# -_V1_3.net
KiCad netlist of a schematic drawn in EasyEDA Pro
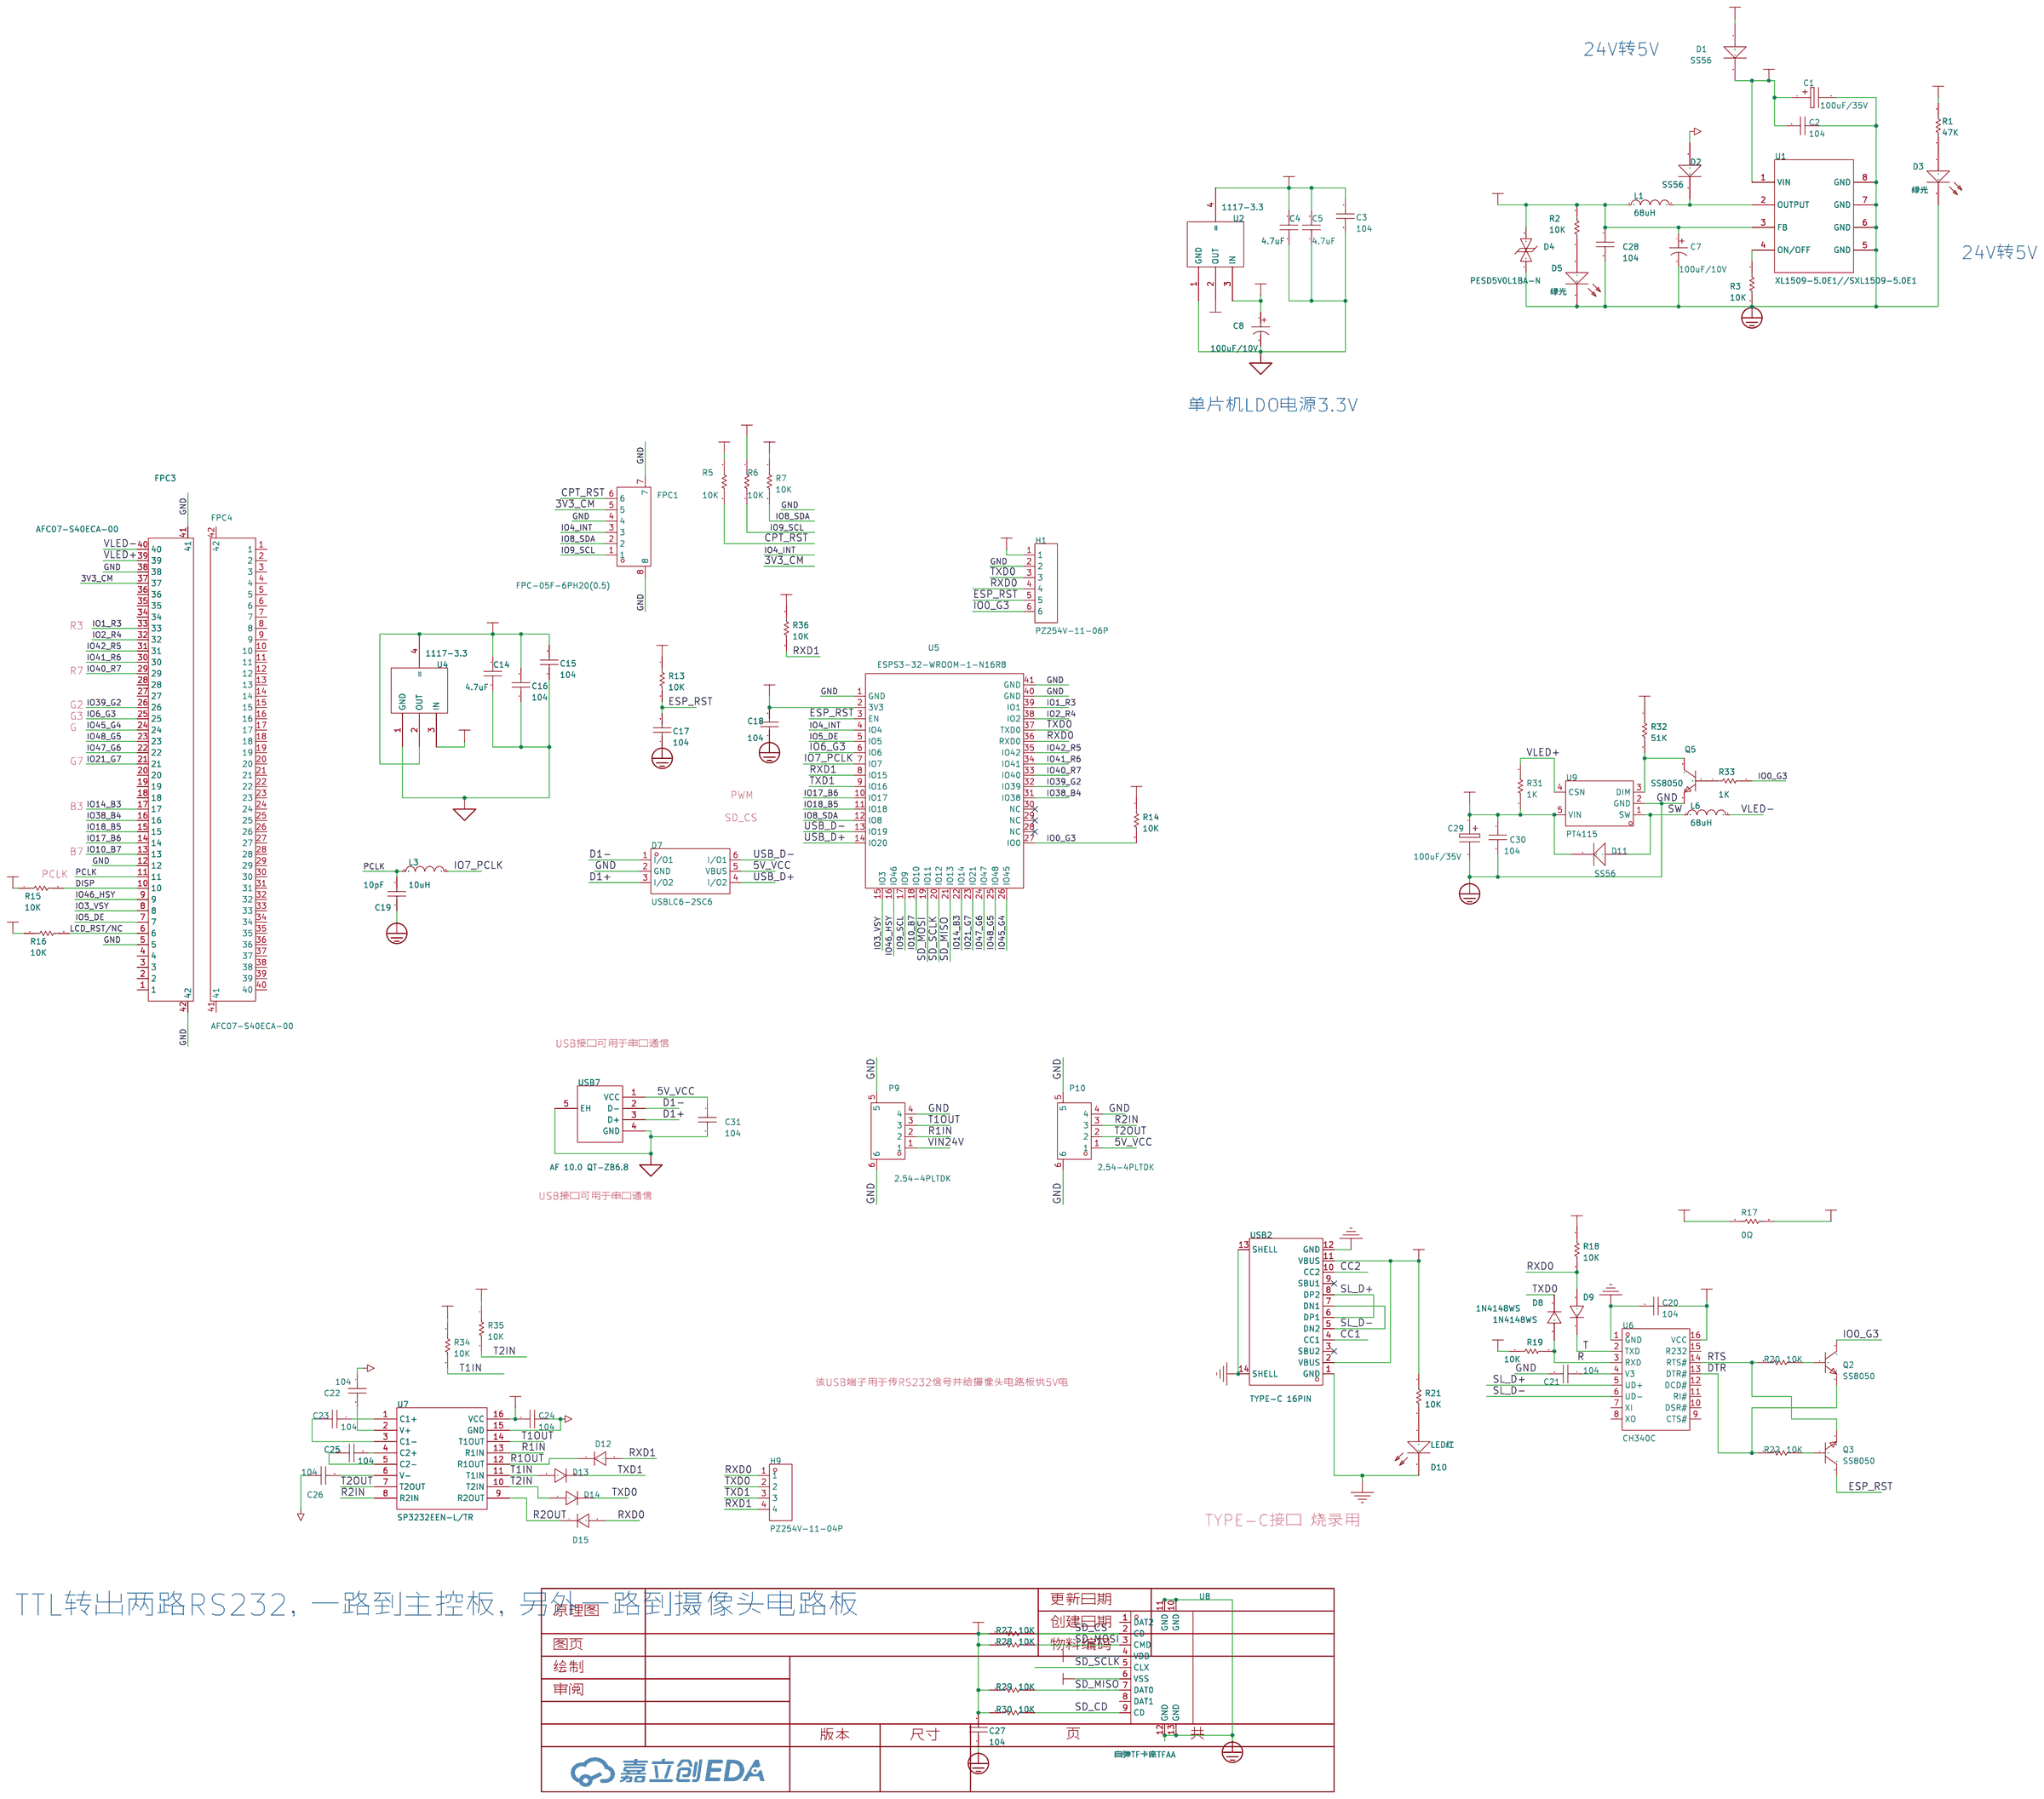
[diagram p0: schematic sheet]

(export (version "E")
  (design (tool "Eeschema 10.0.6"))
  (components
    (comp (ref "C1")
      (value "100uF/35V")
      (footprint "easyedapro:电解电容贴片10x10")
      (libsource (lib "easyedapro") (part "ELECTRO1"))
    )
    (comp (ref "C2")
      (value "104")
      (footprint "easyedapro:0603C")
      (description "Capacitor (Semiconductor SIM Model)")
      (libsource (lib "easyedapro") (part "Cap Semi"))
    )
    (comp (ref "C3")
      (value "104")
      (footprint "easyedapro:0603C")
      (description "Capacitor (Semiconductor SIM Model)")
      (libsource (lib "easyedapro") (part "Cap Semi"))
    )
    (comp (ref "C4") (value "4.7uF") (libsource (lib "easyedapro") (part "CAP")))
    (comp (ref "C5") (value "4.7uF") (libsource (lib "easyedapro") (part "CAP")))
    (comp (ref "C7")
      (value "100uF/10V")
      (footprint "easyedapro:CAP-SMD_BD5.0-L5.3-W5.3-RD")
      (fields (field (name "Manufacturer Part") "CS1A101M-CRD54") (field (name "Manufacturer") "ST(先科)"))
      (libsource (lib "easyedapro") (part "CS1A101M-CRD54"))
    )
    (comp (ref "C8")
      (value "100uF/10V")
      (footprint "easyedapro:CAP-SMD_BD5.0-L5.3-W5.3-RD")
      (fields (field (name "Manufacturer Part") "CS1A101M-CRD54") (field (name "Manufacturer") "ST(先科)"))
      (libsource (lib "easyedapro") (part "CS1A101M-CRD54"))
    )
    (comp (ref "C14") (value "4.7uF") (libsource (lib "easyedapro") (part "CAP")))
    (comp (ref "C15")
      (value "104")
      (footprint "easyedapro:0603C")
      (description "Capacitor (Semiconductor SIM Model)")
      (libsource (lib "easyedapro") (part "Cap Semi"))
    )
    (comp (ref "C16")
      (value "104")
      (footprint "easyedapro:0603C")
      (description "Capacitor (Semiconductor SIM Model)")
      (libsource (lib "easyedapro") (part "Cap Semi"))
    )
    (comp (ref "C17")
      (value "104")
      (footprint "easyedapro:0603C")
      (description "Capacitor (Semiconductor SIM Model)")
      (libsource (lib "easyedapro") (part "Cap Semi"))
    )
    (comp (ref "C18")
      (value "104")
      (footprint "easyedapro:0603C")
      (description "Capacitor (Semiconductor SIM Model)")
      (libsource (lib "easyedapro") (part "Cap Semi"))
    )
    (comp (ref "C19")
      (value "10pF")
      (footprint "easyedapro:0603C")
      (description "Capacitor (Semiconductor SIM Model)")
      (libsource (lib "easyedapro") (part "Cap Semi"))
    )
    (comp (ref "C20")
      (value "104")
      (footprint "easyedapro:0603C")
      (description "Capacitor (Semiconductor SIM Model)")
      (libsource (lib "easyedapro") (part "Cap Semi"))
    )
    (comp (ref "C21")
      (value "104")
      (footprint "easyedapro:0603C")
      (description "Capacitor (Semiconductor SIM Model)")
      (libsource (lib "easyedapro") (part "Cap Semi"))
    )
    (comp (ref "C22")
      (value "104")
      (footprint "easyedapro:0603C")
      (description "Capacitor (Semiconductor SIM Model)")
      (libsource (lib "easyedapro") (part "Cap Semi"))
    )
    (comp (ref "C23")
      (value "104")
      (footprint "easyedapro:0603C")
      (description "Capacitor (Semiconductor SIM Model)")
      (libsource (lib "easyedapro") (part "Cap Semi"))
    )
    (comp (ref "C24")
      (value "104")
      (footprint "easyedapro:0603C")
      (description "Capacitor (Semiconductor SIM Model)")
      (libsource (lib "easyedapro") (part "Cap Semi"))
    )
    (comp (ref "C25")
      (value "104")
      (footprint "easyedapro:0603C")
      (description "Capacitor (Semiconductor SIM Model)")
      (libsource (lib "easyedapro") (part "Cap Semi"))
    )
    (comp (ref "C26")
      (value "104")
      (footprint "easyedapro:0603C")
      (description "Capacitor (Semiconductor SIM Model)")
      (libsource (lib "easyedapro") (part "Cap Semi"))
    )
    (comp (ref "C27")
      (value "104")
      (footprint "easyedapro:11")
      (description "Capacitor (Semiconductor SIM Model)")
      (libsource (lib "easyedapro") (part "Cap Semi"))
    )
    (comp (ref "C28")
      (value "104")
      (footprint "easyedapro:0603C")
      (description "Capacitor (Semiconductor SIM Model)")
      (libsource (lib "easyedapro") (part "Cap Semi"))
    )
    (comp (ref "C29")
      (value "100uF/35V")
      (footprint "easyedapro:电解电容贴片10x10")
      (libsource (lib "easyedapro") (part "ELECTRO1"))
    )
    (comp (ref "C30")
      (value "104")
      (footprint "easyedapro:0603C")
      (description "Capacitor (Semiconductor SIM Model)")
      (libsource (lib "easyedapro") (part "Cap Semi"))
    )
    (comp (ref "C31")
      (value "104")
      (footprint "easyedapro:0603C")
      (description "Capacitor (Semiconductor SIM Model)")
      (libsource (lib "easyedapro") (part "Cap Semi"))
    )
    (comp (ref "D1") (value "SS56") (footprint "easyedapro:SMA") (libsource (lib "") (part "1N4148_1")))
    (comp (ref "D2") (value "SS56") (libsource (lib "easyedapro") (part "1N4148")))
    (comp (ref "D3")
      (value "绿光")
      (footprint "easyedapro:0603LED")
      (libsource (lib "easyedapro") (part "LED"))
    )
    (comp (ref "D4")
      (value "PESD5V0L1BA-N")
      (footprint "easyedapro:SOD-523_L1.2-W0.8-LS1.6-BI")
      (description "极性:Bidirectional;反向关断电压（典型值）:5V (Max);击穿电压（最小值）:6V;箝位电压:15V;峰值脉冲电流（10/1000us）:5A (8/20us);")
      (fields (field (name "Manufacturer") "BORN伯恩半导体"))
      (libsource (lib "easyedapro") (part "PESD5V0S1BBN"))
    )
    (comp (ref "D5")
      (value "绿光")
      (footprint "easyedapro:0603LED")
      (libsource (lib "easyedapro") (part "LED"))
    )
    (comp (ref "D7")
      (value "USBLC6-2SC6")
      (footprint "easyedapro:SOT-23-6_L2.9-W1.6-P0.95-LS2.8-BL")
      (description "最大钳位电压:15V;击穿电压:6V;")
      (fields (field (name "Manufacturer") "UMW(友台半导体)"))
      (libsource (lib "easyedapro") (part "USBLC6-2SC6_C2687116"))
    )
    (comp (ref "D8")
      (value "1N4148WS")
      (footprint "easyedapro:SOD-323_L1.8-W1.3-LS2.5-RD")
      (description "二极管配置:独立式;正向压降(Vf):1.25V@150mA;直流反向耐压(Vr):100V;整流电流:150mA;反向恢复时间(Trr):4ns;")
      (fields (field (name "Manufacturer") "CJ(江苏长电/长晶)"))
      (libsource (lib "easyedapro") (part "1N4148WS T4"))
    )
    (comp (ref "D9")
      (value "1N4148WS")
      (footprint "easyedapro:SOD-323_L1.8-W1.3-LS2.5-RD")
      (description "二极管配置:独立式;正向压降(Vf):1.25V@150mA;直流反向耐压(Vr):100V;整流电流:150mA;反向恢复时间(Trr):4ns;")
      (fields (field (name "Manufacturer") "CJ(江苏长电/长晶)"))
      (libsource (lib "easyedapro") (part "1N4148WS T4"))
    )
    (comp (ref "D10")
      (value "LED红")
      (footprint "easyedapro:0603L")
      (description "Typical BLUE SiC LED")
      (libsource (lib "easyedapro") (part "LED3"))
    )
    (comp (ref "D11") (value "SS56") (libsource (lib "easyedapro") (part "1N4148")))
    (comp (ref "D12")
      (value "1N4148WS")
      (footprint "easyedapro:SOD-323_L1.8-W1.3-LS2.5-RD")
      (description "二极管配置:独立式;正向压降(Vf):1.25V@150mA;直流反向耐压(Vr):100V;整流电流:150mA;反向恢复时间(Trr):4ns;")
      (fields (field (name "Manufacturer") "CJ(江苏长电/长晶)"))
      (libsource (lib "easyedapro") (part "1N4148WS T4"))
    )
    (comp (ref "D13")
      (value "1N4148WS")
      (footprint "easyedapro:SOD-323_L1.8-W1.3-LS2.5-RD")
      (description "二极管配置:独立式;正向压降(Vf):1.25V@150mA;直流反向耐压(Vr):100V;整流电流:150mA;反向恢复时间(Trr):4ns;")
      (fields (field (name "Manufacturer") "CJ(江苏长电/长晶)"))
      (libsource (lib "easyedapro") (part "1N4148WS T4"))
    )
    (comp (ref "D14")
      (value "1N4148WS")
      (footprint "easyedapro:SOD-323_L1.8-W1.3-LS2.5-RD")
      (description "二极管配置:独立式;正向压降(Vf):1.25V@150mA;直流反向耐压(Vr):100V;整流电流:150mA;反向恢复时间(Trr):4ns;")
      (fields (field (name "Manufacturer") "CJ(江苏长电/长晶)"))
      (libsource (lib "easyedapro") (part "1N4148WS T4"))
    )
    (comp (ref "D15")
      (value "1N4148WS")
      (footprint "easyedapro:SOD-323_L1.8-W1.3-LS2.5-RD")
      (description "二极管配置:独立式;正向压降(Vf):1.25V@150mA;直流反向耐压(Vr):100V;整流电流:150mA;反向恢复时间(Trr):4ns;")
      (fields (field (name "Manufacturer") "CJ(江苏长电/长晶)"))
      (libsource (lib "easyedapro") (part "1N4148WS T4"))
    )
    (comp (ref "FPC1")
      (value "FPC-05F-6PH20(0.5)")
      (footprint "easyedapro:FPC-SMD_6P-P0.50_XUNPU_FPC-05F-6PH20")
      (description "锁定特性:翻盖式;触点类型:卧贴;触点数量:6P;间距:0.5mm;安装方式:下接;工作温度:-25°C~+85°C;")
      (fields (field (name "Manufacturer") "XUNPU(讯普)"))
      (libsource (lib "easyedapro") (part "FPC-05F-6PH20"))
    )
    (comp (ref "FPC3")
      (value "AFC07-S40ECA-00")
      (footprint "easyedapro:FPC-SMD_P0.50-40P_LCS-SJ-H2.0")
      (description "锁定特性:抽屉式;触点类型:上接;触点数量:40P;间距:0.5mm;安装方式:卧贴;")
      (fields (field (name "Manufacturer") "JS(钜硕电子)"))
      (libsource (lib "easyedapro") (part "AFC07-S40ECA-00"))
    )
    (comp (ref "FPC4")
      (value "AFC07-S40ECA-00")
      (footprint "easyedapro:FPC-SMD_P0.50-40P_LCS-SJ-H2.0")
      (description "锁定特性:抽屉式;触点类型:上接;触点数量:40P;间距:0.5mm;安装方式:卧贴;")
      (fields (field (name "Manufacturer") "JS(钜硕电子)"))
      (libsource (lib "easyedapro") (part "AFC07-S40ECA-00"))
    )
    (comp (ref "H1")
      (value "PZ254V-11-06P")
      (footprint "easyedapro:HDR-TH_6P-P2.54-V-M")
      (fields (field (name "Manufacturer") "XFCN(兴飞)"))
      (libsource (lib "easyedapro") (part "PZ254V-11-06P"))
    )
    (comp (ref "H9")
      (value "PZ254V-11-04P")
      (footprint "easyedapro:HDR-TH_4P-P2.54-V-M")
      (fields (field (name "Manufacturer") "XFCN(兴飞)"))
      (libsource (lib "easyedapro") (part "PZ254V-11-04P_C2691448"))
    )
    (comp (ref "L1")
      (value "68uH")
      (footprint "easyedapro:IND-SMD_L7.0-W7.0_SMDRI74-330MT")
      (description "电感值:33uH;精度:±20%;额定电流:960mA;饱和电流(Isat):1.8A;类型:屏蔽电感;")
      (fields (field (name "Manufacturer Part") "SMDRI74-330MT") (field (name "Manufacturer") "SXN(顺翔诺)"))
      (libsource (lib "easyedapro") (part "SMDRI74-330MT"))
    )
    (comp (ref "L3")
      (value "10uH")
      (footprint "easyedapro:L0603")
      (description "电感值:10uH;精度:±10%;额定电流:3mA;饱和电流(Isat):-;直流电阻(DCR):1.85Ω;")
      (fields
        (field (name "Manufacturer Part") "SDFL1608S100KTF")
        (field (name "Manufacturer") "Sunlord(顺络)")
      )
      (libsource (lib "easyedapro") (part "SDFL1608S100KTF"))
    )
    (comp (ref "L6")
      (value "68uH")
      (footprint "easyedapro:IND-SMD_L7.0-W7.0_SMDRI74-330MT")
      (description "电感值:33uH;精度:±20%;额定电流:960mA;饱和电流(Isat):1.8A;类型:屏蔽电感;")
      (fields (field (name "Manufacturer Part") "SMDRI74-330MT") (field (name "Manufacturer") "SXN(顺翔诺)"))
      (libsource (lib "easyedapro") (part "SMDRI74-330MT"))
    )
    (comp (ref "P9")
      (value "2.54-4PLTDK")
      (footprint "easyedapro:CONN-SMD_4P-P2.50_SHOU_2.54-4PLTDK")
      (fields (field (name "Manufacturer") "SHOU HAN(首韩)"))
      (libsource (lib "easyedapro") (part "2.54-4PLTDK"))
    )
    (comp (ref "P10")
      (value "2.54-4PLTDK")
      (footprint "easyedapro:CONN-SMD_4P-P2.50_SHOU_2.54-4PLTDK")
      (fields (field (name "Manufacturer") "SHOU HAN(首韩)"))
      (libsource (lib "easyedapro") (part "2.54-4PLTDK"))
    )
    (comp (ref "Q2")
      (value "SS8050")
      (footprint "easyedapro:SOT-23-3_L2.9-W1.3-P1.90-LS2.4-BR")
      (fields (field (name "Manufacturer") "Doeshare(德芯)"))
      (libsource (lib "easyedapro") (part "SS8050_C2931717"))
    )
    (comp (ref "Q3")
      (value "SS8050")
      (footprint "easyedapro:SOT-23-3_L2.9-W1.3-P1.90-LS2.4-BR")
      (fields (field (name "Manufacturer") "Doeshare(德芯)"))
      (libsource (lib "easyedapro") (part "SS8050_C2931717"))
    )
    (comp (ref "Q5")
      (value "SS8050")
      (footprint "easyedapro:SOT-23-3_L2.9-W1.3-P1.90-LS2.4-BR")
      (fields (field (name "Manufacturer") "Doeshare(德芯)"))
      (libsource (lib "easyedapro") (part "SS8050_C2931717"))
    )
    (comp (ref "R1")
      (value "47K")
      (footprint "easyedapro:0603R")
      (description "Resistor")
      (libsource (lib "easyedapro") (part "RES"))
    )
    (comp (ref "R2")
      (value "10K")
      (footprint "easyedapro:0603R")
      (description "Resistor")
      (libsource (lib "easyedapro") (part "RES"))
    )
    (comp (ref "R3")
      (value "10K")
      (footprint "easyedapro:0603R")
      (description "Resistor")
      (libsource (lib "easyedapro") (part "RES"))
    )
    (comp (ref "R5")
      (value "10K")
      (footprint "easyedapro:0603R")
      (description "Resistor")
      (libsource (lib "easyedapro") (part "RES"))
    )
    (comp (ref "R6")
      (value "10K")
      (footprint "easyedapro:0603R")
      (description "Resistor")
      (libsource (lib "easyedapro") (part "RES"))
    )
    (comp (ref "R7")
      (value "10K")
      (footprint "easyedapro:0603R")
      (description "Resistor")
      (libsource (lib "easyedapro") (part "RES"))
    )
    (comp (ref "R13")
      (value "10K")
      (footprint "easyedapro:0603R")
      (description "Resistor")
      (libsource (lib "easyedapro") (part "RES"))
    )
    (comp (ref "R14")
      (value "10K")
      (footprint "easyedapro:0603R")
      (description "Resistor")
      (libsource (lib "easyedapro") (part "RES"))
    )
    (comp (ref "R15")
      (value "10K")
      (footprint "easyedapro:0603R")
      (description "Resistor")
      (libsource (lib "easyedapro") (part "RES"))
    )
    (comp (ref "R16")
      (value "10K")
      (footprint "easyedapro:0603R")
      (description "Resistor")
      (libsource (lib "easyedapro") (part "RES"))
    )
    (comp (ref "R17")
      (value "0Ω")
      (footprint "easyedapro:10")
      (description "Resistor")
      (libsource (lib "easyedapro") (part "RES"))
    )
    (comp (ref "R18")
      (value "10K")
      (footprint "easyedapro:0603R")
      (description "Resistor")
      (libsource (lib "easyedapro") (part "RES"))
    )
    (comp (ref "R19")
      (value "10K")
      (footprint "easyedapro:0603R")
      (description "Resistor")
      (libsource (lib "easyedapro") (part "RES"))
    )
    (comp (ref "R20")
      (value "10K")
      (footprint "easyedapro:10")
      (description "Resistor")
      (libsource (lib "easyedapro") (part "RES"))
    )
    (comp (ref "R21")
      (value "10K")
      (footprint "easyedapro:10")
      (description "Resistor")
      (libsource (lib "easyedapro") (part "RES"))
    )
    (comp (ref "R22")
      (value "10K")
      (footprint "easyedapro:10")
      (description "Resistor")
      (libsource (lib "easyedapro") (part "RES"))
    )
    (comp (ref "R27")
      (value "10K")
      (footprint "easyedapro:10")
      (description "Resistor")
      (libsource (lib "easyedapro") (part "RES"))
    )
    (comp (ref "R28")
      (value "10K")
      (footprint "easyedapro:10")
      (description "Resistor")
      (libsource (lib "easyedapro") (part "RES"))
    )
    (comp (ref "R29")
      (value "10K")
      (footprint "easyedapro:10")
      (description "Resistor")
      (libsource (lib "easyedapro") (part "RES"))
    )
    (comp (ref "R30")
      (value "10K")
      (footprint "easyedapro:10")
      (description "Resistor")
      (libsource (lib "easyedapro") (part "RES"))
    )
    (comp (ref "R31")
      (value "1K")
      (footprint "easyedapro:10")
      (description "Resistor")
      (libsource (lib "easyedapro") (part "RES"))
    )
    (comp (ref "R32")
      (value "51K")
      (footprint "easyedapro:10")
      (description "Resistor")
      (libsource (lib "easyedapro") (part "RES"))
    )
    (comp (ref "R33")
      (value "1K")
      (footprint "easyedapro:10")
      (description "Resistor")
      (libsource (lib "easyedapro") (part "RES"))
    )
    (comp (ref "R34")
      (value "10K")
      (footprint "easyedapro:10")
      (description "Resistor")
      (libsource (lib "easyedapro") (part "RES"))
    )
    (comp (ref "R35")
      (value "10K")
      (footprint "easyedapro:10")
      (description "Resistor")
      (libsource (lib "easyedapro") (part "RES"))
    )
    (comp (ref "R36")
      (value "10K")
      (footprint "easyedapro:0603R")
      (description "Resistor")
      (libsource (lib "easyedapro") (part "RES"))
    )
    (comp (ref "U1")
      (value "XL1509-5.0E1//SXL1509-5.0E1")
      (footprint "easyedapro:SOIC-8_L5.0-W4.0-P1.27-LS6.0-BL")
      (description "功能类型:降压型;同步整流:-;输出通道数:-;拓扑结构:-;输入电压:-;输出电流(最大值):-;开关频率:-;")
      (fields (field (name "Manufacturer") "XLSEMI(芯龙)"))
      (libsource (lib "easyedapro") (part "XL1509-5.0E1"))
    )
    (comp (ref "U2")
      (value "1117-3.3")
      (footprint "easyedapro:SOT-223")
      (libsource (lib "easyedapro") (part "LM1117"))
    )
    (comp (ref "U4")
      (value "1117-3.3")
      (footprint "easyedapro:SOT-223")
      (libsource (lib "easyedapro") (part "LM1117"))
    )
    (comp (ref "U5")
      (value "ESPS3-32-WROOM-1-N16R8")
      (footprint "easyedapro:WIRELM-SMD_ESP32-S3-WROOM-2-N32R8V")
      (description "核心处理器:ESP32-S3R8V芯片;频率:2.4GHz;发射功率:20.5dBm;")
      (fields
        (field (name "Manufacturer Part") "ESP32-S3-WROOM-2-N32R8V")
        (field (name "Manufacturer") "ESPRESSIF(乐鑫)")
      )
      (libsource (lib "easyedapro") (part "ESP32-S3-WROOM-2-N32R8V"))
    )
    (comp (ref "U6")
      (value "CH340C")
      (footprint "easyedapro:SOIC-16_L9.9-W3.9-P1.27-LS6.0-BL")
      (description "应用功能:收发器;接口协议:USB 2.0;数据速率:2Mbps;")
      (fields (field (name "Manufacturer") "WCH(南京沁恒)"))
      (libsource (lib "easyedapro") (part "CH340G"))
    )
    (comp (ref "U7")
      (value "SP3232EEN-L/TR")
      (footprint "easyedapro:SOIC-16_L9.9-W3.9-P1.27-LS6.0-BL")
      (description "类型:收发器;数据速率:235Kbps;")
      (fields (field (name "Manufacturer") "MaxLinear(迈凌)"))
      (libsource (lib "easyedapro") (part "SP3232EEN-L/TR"))
    )
    (comp (ref "U8")
      (value "自弹TF卡座TFAA")
      (footprint "easyedapro:SIM-SMD_C9900015645")
      (libsource (lib "easyedapro") (part "自弹TF卡座TFAA"))
    )
    (comp (ref "U9")
      (value "PT4115")
      (footprint "easyedapro:SOT-89-5_L4.5-W2.5-P1.50-LS4.5-BR")
      (description "类型:DC-DC;工作电压(DC):6V~30V;开关频率:1MHz;通道数:-;输出电压:-;输出电流:1.2A;调光:PWM；模拟;拓扑结构:降压;")
      (fields (field (name "Manufacturer") "UMW(友台半导体)"))
      (libsource (lib "easyedapro") (part "PT4115"))
    )
    (comp (ref "USB2")
      (value "TYPE-C 16PIN")
      (footprint "easyedapro:USB-C-SMD_TYPE-C-6PIN-2MD-073")
      (description "连接器类型:Type-C;标准:-;公母:母;端口数量:1;触点数量:16P;安装方式:卧贴;额定电流 - 电源:5A;工作温度范围:-25°C~+85°C;")
      (fields (field (name "Manufacturer") "SHOU HAN(首韩)"))
      (libsource (lib "easyedapro") (part "TYPE-C 16PIN 2MD(073)"))
    )
    (comp (ref "USB7")
      (value "AF 10.0 QT-ZB6.8")
      (footprint "easyedapro:USB-A-SMD_AF-10.0-QT-ZB6.8")
      (description "连接器类型:Type-A;协议标准:USB 2.0;公母:母;安装方式:卧贴;触点数量:4P;端口数量:1;额定电流 - 电源:1.5A;工作温度:-25°C~+85°C;")
      (fields (field (name "Manufacturer") "SHOU HAN(首韩)"))
      (libsource (lib "easyedapro") (part "AF 10.0 QT-ZB6.8"))
    )
  )
  (nets
    (net (code "1") (name "/CC1") (class "Default")
      (node (ref "USB2") (pin "4") (pinfunction "CC1_4") (pintype "unspecified"))
    )
    (net (code "2") (name "/CC2") (class "Default")
      (node (ref "USB2") (pin "10") (pinfunction "CC2_10") (pintype "unspecified"))
    )
    (net (code "3") (name "/CPT_RST") (class "Default")
      (node (ref "FPC1") (pin "6") (pinfunction "6_6") (pintype "unspecified"))
      (node (ref "R5") (pin "2") (pinfunction "2_2") (pintype "unspecified"))
    )
    (net (code "4") (name "/D1+") (class "Default")
      (node (ref "D7") (pin "3") (pinfunction "I/O2_3") (pintype "unspecified"))
      (node (ref "USB7") (pin "3") (pinfunction "D+_3") (pintype "unspecified"))
    )
    (net (code "5") (name "/D1-") (class "Default")
      (node (ref "D7") (pin "1") (pinfunction "I/O1_1") (pintype "unspecified"))
      (node (ref "USB7") (pin "2") (pinfunction "D-_2") (pintype "unspecified"))
    )
    (net (code "6") (name "/DISP") (class "Default")
      (node (ref "FPC3") (pin "10") (pinfunction "10_10") (pintype "unspecified"))
      (node (ref "R15") (pin "2") (pinfunction "2_2") (pintype "unspecified"))
    )
    (net (code "7") (name "/DTR") (class "Default")
      (node (ref "Q2") (pin "2") (pinfunction "E_2") (pintype "unspecified"))
      (node (ref "R22") (pin "2") (pinfunction "2_2") (pintype "unspecified"))
      (node (ref "U6") (pin "13") (pinfunction "DTR#_13") (pintype "unspecified"))
    )
    (net (code "8") (name "/ESP_RST") (class "Default")
      (node (ref "C17") (pin "2") (pinfunction "2_2") (pintype "unspecified"))
      (node (ref "H1") (pin "5") (pinfunction "5_5") (pintype "unspecified"))
      (node (ref "Q3") (pin "3") (pinfunction "C_3") (pintype "unspecified"))
      (node (ref "R13") (pin "2") (pinfunction "2_2") (pintype "unspecified"))
      (node (ref "U5") (pin "3") (pinfunction "EN_3") (pintype "unspecified"))
    )
    (net (code "9") (name "/IO0_G3") (class "Default")
      (node (ref "H1") (pin "6") (pinfunction "6_6") (pintype "unspecified"))
      (node (ref "Q2") (pin "3") (pinfunction "C_3") (pintype "unspecified"))
      (node (ref "R14") (pin "2") (pinfunction "2_2") (pintype "unspecified"))
      (node (ref "R33") (pin "2") (pinfunction "2_2") (pintype "unspecified"))
      (node (ref "U5") (pin "27") (pinfunction "IO0_27") (pintype "unspecified"))
    )
    (net (code "10") (name "/IO1_R3") (class "Default")
      (node (ref "FPC3") (pin "33") (pinfunction "33_33") (pintype "unspecified"))
      (node (ref "U5") (pin "39") (pinfunction "IO1_39") (pintype "unspecified"))
    )
    (net (code "11") (name "/IO2_R4") (class "Default")
      (node (ref "FPC3") (pin "32") (pinfunction "32_32") (pintype "unspecified"))
      (node (ref "U5") (pin "38") (pinfunction "IO2_38") (pintype "unspecified"))
    )
    (net (code "12") (name "/IO3_VSY") (class "Default")
      (node (ref "FPC3") (pin "8") (pinfunction "8_8") (pintype "unspecified"))
      (node (ref "U5") (pin "15") (pinfunction "IO3_15") (pintype "unspecified"))
    )
    (net (code "13") (name "/IO4_INT") (class "Default")
      (node (ref "FPC1") (pin "3") (pinfunction "3_3") (pintype "unspecified"))
      (node (ref "U5") (pin "4") (pinfunction "IO4_4") (pintype "unspecified"))
    )
    (net (code "14") (name "/IO5_DE") (class "Default")
      (node (ref "FPC3") (pin "7") (pinfunction "7_7") (pintype "unspecified"))
      (node (ref "U5") (pin "5") (pinfunction "IO5_5") (pintype "unspecified"))
    )
    (net (code "15") (name "/IO6_G3") (class "Default")
      (node (ref "FPC3") (pin "25") (pinfunction "25_25") (pintype "unspecified"))
      (node (ref "U5") (pin "6") (pinfunction "IO6_6") (pintype "unspecified"))
    )
    (net (code "16") (name "/IO7_PCLK") (class "Default")
      (node (ref "L3") (pin "2") (pinfunction "2_2") (pintype "unspecified"))
      (node (ref "U5") (pin "7") (pinfunction "IO7_7") (pintype "unspecified"))
    )
    (net (code "17") (name "/IO8_SDA") (class "Default")
      (node (ref "FPC1") (pin "2") (pinfunction "2_2") (pintype "unspecified"))
      (node (ref "R7") (pin "2") (pinfunction "2_2") (pintype "unspecified"))
      (node (ref "U5") (pin "12") (pinfunction "IO8_12") (pintype "unspecified"))
    )
    (net (code "18") (name "/IO9_SCL") (class "Default")
      (node (ref "FPC1") (pin "1") (pinfunction "1_1") (pintype "unspecified"))
      (node (ref "R6") (pin "2") (pinfunction "2_2") (pintype "unspecified"))
      (node (ref "U5") (pin "17") (pinfunction "IO9_17") (pintype "unspecified"))
    )
    (net (code "19") (name "/IO10_B7") (class "Default")
      (node (ref "FPC3") (pin "13") (pinfunction "13_13") (pintype "unspecified"))
      (node (ref "U5") (pin "18") (pinfunction "IO10_18") (pintype "unspecified"))
    )
    (net (code "20") (name "/IO14_B3") (class "Default")
      (node (ref "FPC3") (pin "17") (pinfunction "17_17") (pintype "unspecified"))
      (node (ref "U5") (pin "22") (pinfunction "IO14_22") (pintype "unspecified"))
    )
    (net (code "21") (name "/IO17_B6") (class "Default")
      (node (ref "FPC3") (pin "14") (pinfunction "14_14") (pintype "unspecified"))
      (node (ref "U5") (pin "10") (pinfunction "IO17_10") (pintype "unspecified"))
    )
    (net (code "22") (name "/IO18_B5") (class "Default")
      (node (ref "FPC3") (pin "15") (pinfunction "15_15") (pintype "unspecified"))
      (node (ref "U5") (pin "11") (pinfunction "IO18_11") (pintype "unspecified"))
    )
    (net (code "23") (name "/IO21_G7") (class "Default")
      (node (ref "FPC3") (pin "21") (pinfunction "21_21") (pintype "unspecified"))
      (node (ref "U5") (pin "23") (pinfunction "IO21_23") (pintype "unspecified"))
    )
    (net (code "24") (name "/IO38_B4") (class "Default")
      (node (ref "FPC3") (pin "16") (pinfunction "16_16") (pintype "unspecified"))
      (node (ref "U5") (pin "31") (pinfunction "IO38_31") (pintype "unspecified"))
    )
    (net (code "25") (name "/IO39_G2") (class "Default")
      (node (ref "FPC3") (pin "26") (pinfunction "26_26") (pintype "unspecified"))
      (node (ref "U5") (pin "32") (pinfunction "IO39_32") (pintype "unspecified"))
    )
    (net (code "26") (name "/IO40_R7") (class "Default")
      (node (ref "FPC3") (pin "29") (pinfunction "29_29") (pintype "unspecified"))
      (node (ref "U5") (pin "33") (pinfunction "IO40_33") (pintype "unspecified"))
    )
    (net (code "27") (name "/IO41_R6") (class "Default")
      (node (ref "FPC3") (pin "30") (pinfunction "30_30") (pintype "unspecified"))
      (node (ref "U5") (pin "34") (pinfunction "IO41_34") (pintype "unspecified"))
    )
    (net (code "28") (name "/IO42_R5") (class "Default")
      (node (ref "FPC3") (pin "31") (pinfunction "31_31") (pintype "unspecified"))
      (node (ref "U5") (pin "35") (pinfunction "IO42_35") (pintype "unspecified"))
    )
    (net (code "29") (name "/IO45_G4") (class "Default")
      (node (ref "FPC3") (pin "24") (pinfunction "24_24") (pintype "unspecified"))
      (node (ref "U5") (pin "26") (pinfunction "IO45_26") (pintype "unspecified"))
    )
    (net (code "30") (name "/IO46_HSY") (class "Default")
      (node (ref "FPC3") (pin "9") (pinfunction "9_9") (pintype "unspecified"))
      (node (ref "U5") (pin "16") (pinfunction "IO46_16") (pintype "unspecified"))
    )
    (net (code "31") (name "/IO47_G6") (class "Default")
      (node (ref "FPC3") (pin "22") (pinfunction "22_22") (pintype "unspecified"))
      (node (ref "U5") (pin "24") (pinfunction "IO47_24") (pintype "unspecified"))
    )
    (net (code "32") (name "/IO48_G5") (class "Default")
      (node (ref "FPC3") (pin "23") (pinfunction "23_23") (pintype "unspecified"))
      (node (ref "U5") (pin "25") (pinfunction "IO48_25") (pintype "unspecified"))
    )
    (net (code "33") (name "/LCD_RST{slash}NC") (class "Default")
      (node (ref "FPC3") (pin "6") (pinfunction "6_6") (pintype "unspecified"))
      (node (ref "R16") (pin "2") (pinfunction "2_2") (pintype "unspecified"))
    )
    (net (code "34") (name "/PCLK") (class "Default")
      (node (ref "C19") (pin "2") (pinfunction "2_2") (pintype "unspecified"))
      (node (ref "FPC3") (pin "11") (pinfunction "11_11") (pintype "unspecified"))
      (node (ref "L3") (pin "1") (pinfunction "1_1") (pintype "unspecified"))
    )
    (net (code "35") (name "/R") (class "Default")
      (node (ref "D8") (pin "2") (pinfunction "A_2") (pintype "unspecified"))
      (node (ref "R19") (pin "2") (pinfunction "2_2") (pintype "unspecified"))
      (node (ref "U6") (pin "3") (pinfunction "RXD_3") (pintype "unspecified"))
    )
    (net (code "36") (name "/R1IN") (class "Default")
      (node (ref "P9") (pin "2") (pinfunction "2_2") (pintype "unspecified"))
      (node (ref "U7") (pin "13") (pinfunction "R1IN_13") (pintype "unspecified"))
    )
    (net (code "37") (name "/R1OUT") (class "Default")
      (node (ref "D12") (pin "1") (pinfunction "K_1") (pintype "unspecified"))
      (node (ref "U7") (pin "12") (pinfunction "R1OUT_12") (pintype "unspecified"))
    )
    (net (code "38") (name "/R2IN") (class "Default")
      (node (ref "P10") (pin "3") (pinfunction "3_3") (pintype "unspecified"))
      (node (ref "U7") (pin "8") (pinfunction "R2IN_8") (pintype "unspecified"))
    )
    (net (code "39") (name "/R2OUT") (class "Default")
      (node (ref "D15") (pin "1") (pinfunction "K_1") (pintype "unspecified"))
      (node (ref "U7") (pin "9") (pinfunction "R2OUT_9") (pintype "unspecified"))
    )
    (net (code "40") (name "/RTS") (class "Default")
      (node (ref "Q3") (pin "2") (pinfunction "E_2") (pintype "unspecified"))
      (node (ref "R20") (pin "2") (pinfunction "2_2") (pintype "unspecified"))
      (node (ref "U6") (pin "14") (pinfunction "RTS#_14") (pintype "unspecified"))
    )
    (net (code "41") (name "/RXD0") (class "Default")
      (node (ref "D15") (pin "2") (pinfunction "A_2") (pintype "unspecified"))
      (node (ref "D9") (pin "2") (pinfunction "A_2") (pintype "unspecified"))
      (node (ref "H1") (pin "4") (pinfunction "4_4") (pintype "unspecified"))
      (node (ref "H9") (pin "1") (pinfunction "1_1") (pintype "unspecified"))
      (node (ref "R18") (pin "1") (pinfunction "1_1") (pintype "unspecified"))
      (node (ref "U5") (pin "36") (pinfunction "RXD0_36") (pintype "unspecified"))
    )
    (net (code "42") (name "/RXD1") (class "Default")
      (node (ref "D12") (pin "2") (pinfunction "A_2") (pintype "unspecified"))
      (node (ref "H9") (pin "4") (pinfunction "4_4") (pintype "unspecified"))
      (node (ref "R36") (pin "2") (pinfunction "2_2") (pintype "unspecified"))
      (node (ref "U5") (pin "8") (pinfunction "IO15_8") (pintype "unspecified"))
    )
    (net (code "43") (name "/SD_CD") (class "Default")
      (node (ref "R30") (pin "1") (pinfunction "1_1") (pintype "unspecified"))
      (node (ref "U8") (pin "9") (pinfunction "CD_9") (pintype "unspecified"))
    )
    (net (code "44") (name "/SD_CS") (class "Default")
      (node (ref "R27") (pin "1") (pinfunction "1_1") (pintype "unspecified"))
      (node (ref "U8") (pin "2") (pinfunction "CD_2") (pintype "unspecified"))
    )
    (net (code "45") (name "/SD_MISO") (class "Default")
      (node (ref "R29") (pin "1") (pinfunction "1_1") (pintype "unspecified"))
      (node (ref "U5") (pin "21") (pinfunction "IO13_21") (pintype "unspecified"))
      (node (ref "U8") (pin "7") (pinfunction "DAT0_7") (pintype "unspecified"))
    )
    (net (code "46") (name "/SD_MOSI") (class "Default")
      (node (ref "R28") (pin "1") (pinfunction "1_1") (pintype "unspecified"))
      (node (ref "U5") (pin "19") (pinfunction "IO11_19") (pintype "unspecified"))
      (node (ref "U8") (pin "3") (pinfunction "CMD_3") (pintype "unspecified"))
    )
    (net (code "47") (name "/SD_SCLK") (class "Default")
      (node (ref "U5") (pin "20") (pinfunction "IO12_20") (pintype "unspecified"))
      (node (ref "U8") (pin "5") (pinfunction "CLX_5") (pintype "unspecified"))
    )
    (net (code "48") (name "/SL_D+") (class "Default")
      (node (ref "U6") (pin "5") (pinfunction "UD+_5") (pintype "unspecified"))
      (node (ref "USB2") (pin "6") (pinfunction "DP1_6") (pintype "unspecified"))
      (node (ref "USB2") (pin "8") (pinfunction "DP2_8") (pintype "unspecified"))
    )
    (net (code "49") (name "/SL_D-") (class "Default")
      (node (ref "U6") (pin "6") (pinfunction "UD-_6") (pintype "unspecified"))
      (node (ref "USB2") (pin "5") (pinfunction "DN2_5") (pintype "unspecified"))
      (node (ref "USB2") (pin "7") (pinfunction "DN1_7") (pintype "unspecified"))
    )
    (net (code "50") (name "/SW") (class "Default")
      (node (ref "D11") (pin "1") (pinfunction "1_1") (pintype "input"))
      (node (ref "L6") (pin "1") (pinfunction "1_1") (pintype "unspecified"))
      (node (ref "U9") (pin "1") (pinfunction "SW_1") (pintype "unspecified"))
    )
    (net (code "51") (name "/T") (class "Default")
      (node (ref "D9") (pin "1") (pinfunction "K_1") (pintype "unspecified"))
      (node (ref "U6") (pin "2") (pinfunction "TXD_2") (pintype "unspecified"))
    )
    (net (code "52") (name "/T1IN") (class "Default")
      (node (ref "D13") (pin "2") (pinfunction "A_2") (pintype "unspecified"))
      (node (ref "R34") (pin "2") (pinfunction "2_2") (pintype "unspecified"))
      (node (ref "U7") (pin "11") (pinfunction "T1IN_11") (pintype "unspecified"))
    )
    (net (code "53") (name "/T1OUT") (class "Default")
      (node (ref "P9") (pin "3") (pinfunction "3_3") (pintype "unspecified"))
      (node (ref "U7") (pin "14") (pinfunction "T1OUT_14") (pintype "unspecified"))
    )
    (net (code "54") (name "/T2IN") (class "Default")
      (node (ref "D14") (pin "2") (pinfunction "A_2") (pintype "unspecified"))
      (node (ref "R35") (pin "2") (pinfunction "2_2") (pintype "unspecified"))
      (node (ref "U7") (pin "10") (pinfunction "T2IN_10") (pintype "unspecified"))
    )
    (net (code "55") (name "/T2OUT") (class "Default")
      (node (ref "P10") (pin "2") (pinfunction "2_2") (pintype "unspecified"))
      (node (ref "U7") (pin "7") (pinfunction "T2OUT_7") (pintype "unspecified"))
    )
    (net (code "56") (name "/TXD0") (class "Default")
      (node (ref "D14") (pin "1") (pinfunction "K_1") (pintype "unspecified"))
      (node (ref "D8") (pin "1") (pinfunction "K_1") (pintype "unspecified"))
      (node (ref "H1") (pin "3") (pinfunction "3_3") (pintype "unspecified"))
      (node (ref "H9") (pin "2") (pinfunction "2_2") (pintype "unspecified"))
      (node (ref "U5") (pin "37") (pinfunction "TXD0_37") (pintype "unspecified"))
    )
    (net (code "57") (name "/TXD1") (class "Default")
      (node (ref "D13") (pin "1") (pinfunction "K_1") (pintype "unspecified"))
      (node (ref "H9") (pin "3") (pinfunction "3_3") (pintype "unspecified"))
      (node (ref "U5") (pin "9") (pinfunction "IO16_9") (pintype "unspecified"))
    )
    (net (code "58") (name "/USB_D+") (class "Default")
      (node (ref "D7") (pin "4") (pinfunction "I/O2_4") (pintype "unspecified"))
      (node (ref "U5") (pin "14") (pinfunction "IO20_14") (pintype "unspecified"))
    )
    (net (code "59") (name "/USB_D-") (class "Default")
      (node (ref "D7") (pin "6") (pinfunction "I/O1_6") (pintype "unspecified"))
      (node (ref "U5") (pin "13") (pinfunction "IO19_13") (pintype "unspecified"))
    )
    (net (code "60") (name "/VLED+") (class "Default")
      (node (ref "FPC3") (pin "39") (pinfunction "39_39") (pintype "unspecified"))
      (node (ref "R31") (pin "2") (pinfunction "2_2") (pintype "unspecified"))
      (node (ref "U9") (pin "4") (pinfunction "CSN_4") (pintype "unspecified"))
    )
    (net (code "61") (name "/VLED-") (class "Default")
      (node (ref "FPC3") (pin "40") (pinfunction "40_40") (pintype "unspecified"))
      (node (ref "L6") (pin "2") (pinfunction "2_2") (pintype "unspecified"))
    )
    (net (code "62") (name "3V3") (class "Default")
      (node (ref "C18") (pin "2") (pinfunction "2_2") (pintype "unspecified"))
      (node (ref "C27") (pin "2") (pinfunction "2_2") (pintype "unspecified"))
      (node (ref "C3") (pin "2") (pinfunction "2_2") (pintype "unspecified"))
      (node (ref "C4") (pin "2") (pinfunction "2_2") (pintype "input"))
      (node (ref "C5") (pin "2") (pinfunction "2_2") (pintype "input"))
      (node (ref "R13") (pin "1") (pinfunction "1_1") (pintype "unspecified"))
      (node (ref "R14") (pin "1") (pinfunction "1_1") (pintype "unspecified"))
      (node (ref "R18") (pin "2") (pinfunction "2_2") (pintype "unspecified"))
      (node (ref "R27") (pin "2") (pinfunction "2_2") (pintype "unspecified"))
      (node (ref "R28") (pin "2") (pinfunction "2_2") (pintype "unspecified"))
      (node (ref "R29") (pin "2") (pinfunction "2_2") (pintype "unspecified"))
      (node (ref "R30") (pin "2") (pinfunction "2_2") (pintype "unspecified"))
      (node (ref "R36") (pin "1") (pinfunction "1_1") (pintype "unspecified"))
      (node (ref "U2") (pin "2") (pinfunction "OUT_2") (pintype "unspecified"))
      (node (ref "U2") (pin "4") (pinfunction "=_4") (pintype "unspecified"))
      (node (ref "U5") (pin "2") (pinfunction "3V3_2") (pintype "unspecified"))
      (node (ref "U8") (pin "4") (pinfunction "VDD_4") (pintype "unspecified"))
    )
    (net (code "63") (name "3V3_CM") (class "Default")
      (node (ref "C14") (pin "2") (pinfunction "2_2") (pintype "input"))
      (node (ref "C15") (pin "2") (pinfunction "2_2") (pintype "unspecified"))
      (node (ref "C16") (pin "2") (pinfunction "2_2") (pintype "unspecified"))
      (node (ref "FPC1") (pin "5") (pinfunction "5_5") (pintype "unspecified"))
      (node (ref "FPC3") (pin "37") (pinfunction "37_37") (pintype "unspecified"))
      (node (ref "R15") (pin "1") (pinfunction "1_1") (pintype "unspecified"))
      (node (ref "R16") (pin "1") (pinfunction "1_1") (pintype "unspecified"))
      (node (ref "R5") (pin "1") (pinfunction "1_1") (pintype "unspecified"))
      (node (ref "R6") (pin "1") (pinfunction "1_1") (pintype "unspecified"))
      (node (ref "R7") (pin "1") (pinfunction "1_1") (pintype "unspecified"))
      (node (ref "U4") (pin "2") (pinfunction "OUT_2") (pintype "unspecified"))
      (node (ref "U4") (pin "4") (pinfunction "=_4") (pintype "unspecified"))
    )
    (net (code "64") (name "5V_SHAOLU") (class "Default")
      (node (ref "R17") (pin "1") (pinfunction "1_1") (pintype "unspecified"))
      (node (ref "R21") (pin "1") (pinfunction "1_1") (pintype "unspecified"))
      (node (ref "USB2") (pin "11") (pinfunction "VBUS_11") (pintype "unspecified"))
      (node (ref "USB2") (pin "2") (pinfunction "VBUS_2") (pintype "unspecified"))
    )
    (net (code "65") (name "5V_VCC") (class "Default")
      (node (ref "C20") (pin "1") (pinfunction "1_1") (pintype "unspecified"))
      (node (ref "C24") (pin "2") (pinfunction "2_2") (pintype "unspecified"))
      (node (ref "C28") (pin "1") (pinfunction "1_1") (pintype "unspecified"))
      (node (ref "C31") (pin "1") (pinfunction "1_1") (pintype "unspecified"))
      (node (ref "C7") (pin "1") (pinfunction "1_1") (pintype "input"))
      (node (ref "C8") (pin "1") (pinfunction "1_1") (pintype "input"))
      (node (ref "D4") (pin "2") (pinfunction "2_2") (pintype "input"))
      (node (ref "D7") (pin "5") (pinfunction "VBUS_5") (pintype "unspecified"))
      (node (ref "H1") (pin "1") (pinfunction "1_1") (pintype "unspecified"))
      (node (ref "L1") (pin "1") (pinfunction "1_1") (pintype "unspecified"))
      (node (ref "P10") (pin "1") (pinfunction "1_1") (pintype "unspecified"))
      (node (ref "R17") (pin "2") (pinfunction "2_2") (pintype "unspecified"))
      (node (ref "R19") (pin "1") (pinfunction "1_1") (pintype "unspecified"))
      (node (ref "R2") (pin "2") (pinfunction "2_2") (pintype "unspecified"))
      (node (ref "R34") (pin "1") (pinfunction "1_1") (pintype "unspecified"))
      (node (ref "R35") (pin "1") (pinfunction "1_1") (pintype "unspecified"))
      (node (ref "U1") (pin "3") (pinfunction "FB_3") (pintype "input"))
      (node (ref "U2") (pin "3") (pinfunction "IN_3") (pintype "unspecified"))
      (node (ref "U4") (pin "3") (pinfunction "IN_3") (pintype "unspecified"))
      (node (ref "U6") (pin "16") (pinfunction "VCC_16") (pintype "unspecified"))
      (node (ref "U7") (pin "16") (pinfunction "VCC_16") (pintype "unspecified"))
      (node (ref "USB7") (pin "1") (pinfunction "VCC_1") (pintype "unspecified"))
    )
    (net (code "66") (name "24V_D1") (class "Default")
      (node (ref "C1") (pin "1") (pintype "unspecified"))
      (node (ref "C2") (pin "2") (pinfunction "2_2") (pintype "unspecified"))
      (node (ref "C29") (pin "1") (pintype "unspecified"))
      (node (ref "C30") (pin "1") (pinfunction "1_1") (pintype "unspecified"))
      (node (ref "D1") (pin "2") (pinfunction "2_2") (pintype "unspecified"))
      (node (ref "D11") (pin "2") (pinfunction "2_2") (pintype "input"))
      (node (ref "R1") (pin "2") (pinfunction "2_2") (pintype "unspecified"))
      (node (ref "R31") (pin "1") (pinfunction "1_1") (pintype "unspecified"))
      (node (ref "R32") (pin "1") (pinfunction "1_1") (pintype "unspecified"))
      (node (ref "U1") (pin "1") (pinfunction "VIN_1") (pintype "input"))
      (node (ref "U9") (pin "5") (pinfunction "VIN_5") (pintype "unspecified"))
    )
    (net (code "67") (name "GND") (class "Default")
      (node (ref "C1") (pin "2") (pintype "unspecified"))
      (node (ref "C14") (pin "1") (pinfunction "1_1") (pintype "input"))
      (node (ref "C15") (pin "1") (pinfunction "1_1") (pintype "unspecified"))
      (node (ref "C16") (pin "1") (pinfunction "1_1") (pintype "unspecified"))
      (node (ref "C17") (pin "1") (pinfunction "1_1") (pintype "unspecified"))
      (node (ref "C18") (pin "1") (pinfunction "1_1") (pintype "unspecified"))
      (node (ref "C19") (pin "1") (pinfunction "1_1") (pintype "unspecified"))
      (node (ref "C2") (pin "1") (pinfunction "1_1") (pintype "unspecified"))
      (node (ref "C20") (pin "2") (pinfunction "2_2") (pintype "unspecified"))
      (node (ref "C21") (pin "2") (pinfunction "2_2") (pintype "unspecified"))
      (node (ref "C22") (pin "1") (pinfunction "1_1") (pintype "unspecified"))
      (node (ref "C24") (pin "1") (pinfunction "1_1") (pintype "unspecified"))
      (node (ref "C26") (pin "2") (pinfunction "2_2") (pintype "unspecified"))
      (node (ref "C27") (pin "1") (pinfunction "1_1") (pintype "unspecified"))
      (node (ref "C28") (pin "2") (pinfunction "2_2") (pintype "unspecified"))
      (node (ref "C29") (pin "2") (pintype "unspecified"))
      (node (ref "C3") (pin "1") (pinfunction "1_1") (pintype "unspecified"))
      (node (ref "C30") (pin "2") (pinfunction "2_2") (pintype "unspecified"))
      (node (ref "C31") (pin "2") (pinfunction "2_2") (pintype "unspecified"))
      (node (ref "C4") (pin "1") (pinfunction "1_1") (pintype "input"))
      (node (ref "C5") (pin "1") (pinfunction "1_1") (pintype "input"))
      (node (ref "C7") (pin "2") (pinfunction "2_2") (pintype "input"))
      (node (ref "C8") (pin "2") (pinfunction "2_2") (pintype "input"))
      (node (ref "D10") (pin "2") (pinfunction "K_2") (pintype "unspecified"))
      (node (ref "D2") (pin "1") (pinfunction "1_1") (pintype "input"))
      (node (ref "D3") (pin "2") (pinfunction "2_2") (pintype "unspecified"))
      (node (ref "D4") (pin "1") (pinfunction "1_1") (pintype "input"))
      (node (ref "D5") (pin "2") (pinfunction "2_2") (pintype "unspecified"))
      (node (ref "D7") (pin "2") (pinfunction "GND_2") (pintype "unspecified"))
      (node (ref "FPC1") (pin "4") (pinfunction "4_4") (pintype "unspecified"))
      (node (ref "FPC1") (pin "7") (pinfunction "7_7") (pintype "unspecified"))
      (node (ref "FPC1") (pin "8") (pinfunction "8_8") (pintype "unspecified"))
      (node (ref "FPC3") (pin "12") (pinfunction "12_12") (pintype "unspecified"))
      (node (ref "FPC3") (pin "38") (pinfunction "38_38") (pintype "unspecified"))
      (node (ref "FPC3") (pin "41") (pinfunction "41_41") (pintype "unspecified"))
      (node (ref "FPC3") (pin "42") (pinfunction "42_42") (pintype "unspecified"))
      (node (ref "FPC3") (pin "5") (pinfunction "5_5") (pintype "unspecified"))
      (node (ref "H1") (pin "2") (pinfunction "2_2") (pintype "unspecified"))
      (node (ref "P10") (pin "4") (pinfunction "4_4") (pintype "unspecified"))
      (node (ref "P10") (pin "5") (pinfunction "5_5") (pintype "unspecified"))
      (node (ref "P10") (pin "6") (pinfunction "6_6") (pintype "unspecified"))
      (node (ref "P9") (pin "4") (pinfunction "4_4") (pintype "unspecified"))
      (node (ref "P9") (pin "5") (pinfunction "5_5") (pintype "unspecified"))
      (node (ref "P9") (pin "6") (pinfunction "6_6") (pintype "unspecified"))
      (node (ref "Q5") (pin "2") (pinfunction "E_2") (pintype "unspecified"))
      (node (ref "R3") (pin "2") (pinfunction "2_2") (pintype "unspecified"))
      (node (ref "U1") (pin "5") (pinfunction "GND_5") (pintype "input"))
      (node (ref "U1") (pin "6") (pinfunction "GND_6") (pintype "input"))
      (node (ref "U1") (pin "7") (pinfunction "GND_7") (pintype "input"))
      (node (ref "U1") (pin "8") (pinfunction "GND_8") (pintype "input"))
      (node (ref "U2") (pin "1") (pinfunction "GND_1") (pintype "unspecified"))
      (node (ref "U4") (pin "1") (pinfunction "GND_1") (pintype "unspecified"))
      (node (ref "U5") (pin "1") (pinfunction "GND_1") (pintype "unspecified"))
      (node (ref "U5") (pin "40") (pinfunction "GND_40") (pintype "unspecified"))
      (node (ref "U5") (pin "41") (pinfunction "GND_41") (pintype "unspecified"))
      (node (ref "U6") (pin "1") (pinfunction "GND_1") (pintype "unspecified"))
      (node (ref "U7") (pin "15") (pinfunction "GND_15") (pintype "unspecified"))
      (node (ref "U8") (pin "10") (pinfunction "GND_10") (pintype "unspecified"))
      (node (ref "U8") (pin "11") (pinfunction "GND_11") (pintype "unspecified"))
      (node (ref "U8") (pin "12") (pinfunction "GND_12") (pintype "unspecified"))
      (node (ref "U8") (pin "13") (pinfunction "GND_13") (pintype "unspecified"))
      (node (ref "U8") (pin "6") (pinfunction "VSS_6") (pintype "unspecified"))
      (node (ref "U9") (pin "2") (pinfunction "GND_2") (pintype "unspecified"))
      (node (ref "USB2") (pin "1") (pinfunction "GND_1") (pintype "unspecified"))
      (node (ref "USB2") (pin "12") (pinfunction "GND_12") (pintype "unspecified"))
      (node (ref "USB2") (pin "13") (pinfunction "SHELL_13") (pintype "unspecified"))
      (node (ref "USB2") (pin "14") (pinfunction "SHELL_14") (pintype "unspecified"))
      (node (ref "USB7") (pin "4") (pinfunction "GND_4") (pintype "unspecified"))
      (node (ref "USB7") (pin "5") (pinfunction "EH_5") (pintype "unspecified"))
    )
    (net (code "68") (name "Net-(D3-Pad1)") (class "Default")
      (node (ref "D3") (pin "1") (pinfunction "1_1") (pintype "unspecified"))
      (node (ref "R1") (pin "1") (pinfunction "1_1") (pintype "unspecified"))
    )
    (net (code "69") (name "Net-(D5-Pad1)") (class "Default")
      (node (ref "D5") (pin "1") (pinfunction "1_1") (pintype "unspecified"))
      (node (ref "R2") (pin "1") (pinfunction "1_1") (pintype "unspecified"))
    )
    (net (code "70") (name "Net-(D10-A)") (class "Default")
      (node (ref "D10") (pin "1") (pinfunction "A_1") (pintype "unspecified"))
      (node (ref "R21") (pin "2") (pinfunction "2_2") (pintype "unspecified"))
    )
    (net (code "71") (name "Net-(Q2-B)") (class "Default")
      (node (ref "Q2") (pin "1") (pinfunction "B_1") (pintype "unspecified"))
      (node (ref "R20") (pin "1") (pinfunction "1_1") (pintype "unspecified"))
    )
    (net (code "72") (name "Net-(Q3-B)") (class "Default")
      (node (ref "Q3") (pin "1") (pinfunction "B_1") (pintype "unspecified"))
      (node (ref "R22") (pin "1") (pinfunction "1_1") (pintype "unspecified"))
    )
    (net (code "73") (name "Net-(Q5-B)") (class "Default")
      (node (ref "Q5") (pin "1") (pinfunction "B_1") (pintype "unspecified"))
      (node (ref "R33") (pin "1") (pinfunction "1_1") (pintype "unspecified"))
    )
    (net (code "74") (name "Net-(Q5-C)") (class "Default")
      (node (ref "Q5") (pin "3") (pinfunction "C_3") (pintype "unspecified"))
      (node (ref "R32") (pin "2") (pinfunction "2_2") (pintype "unspecified"))
      (node (ref "U9") (pin "3") (pinfunction "DIM_3") (pintype "unspecified"))
    )
    (net (code "75") (name "Net-(U1-ON{slash}OFF)") (class "Default")
      (node (ref "R3") (pin "1") (pinfunction "1_1") (pintype "unspecified"))
      (node (ref "U1") (pin "4") (pinfunction "ON/OFF_4") (pintype "input"))
    )
    (net (code "76") (name "Net-(U1-OUTPUT)") (class "Default")
      (node (ref "D2") (pin "2") (pinfunction "2_2") (pintype "input"))
      (node (ref "L1") (pin "2") (pinfunction "2_2") (pintype "unspecified"))
      (node (ref "U1") (pin "2") (pinfunction "OUTPUT_2") (pintype "input"))
    )
    (net (code "77") (name "Net-(U6-V3)") (class "Default")
      (node (ref "C21") (pin "1") (pinfunction "1_1") (pintype "unspecified"))
      (node (ref "U6") (pin "4") (pinfunction "V3_4") (pintype "unspecified"))
    )
    (net (code "78") (name "Net-(U7-C1+)") (class "Default")
      (node (ref "C23") (pin "2") (pinfunction "2_2") (pintype "unspecified"))
      (node (ref "U7") (pin "1") (pinfunction "C1+_1") (pintype "unspecified"))
    )
    (net (code "79") (name "Net-(U7-C1-)") (class "Default")
      (node (ref "C23") (pin "1") (pinfunction "1_1") (pintype "unspecified"))
      (node (ref "U7") (pin "3") (pinfunction "C1-_3") (pintype "unspecified"))
    )
    (net (code "80") (name "Net-(U7-C2+)") (class "Default")
      (node (ref "C25") (pin "2") (pinfunction "2_2") (pintype "unspecified"))
      (node (ref "U7") (pin "4") (pinfunction "C2+_4") (pintype "unspecified"))
    )
    (net (code "81") (name "Net-(U7-C2-)") (class "Default")
      (node (ref "C25") (pin "1") (pinfunction "1_1") (pintype "unspecified"))
      (node (ref "U7") (pin "5") (pinfunction "C2-_5") (pintype "unspecified"))
    )
    (net (code "82") (name "Net-(U7-V+)") (class "Default")
      (node (ref "C22") (pin "2") (pinfunction "2_2") (pintype "unspecified"))
      (node (ref "U7") (pin "2") (pinfunction "V+_2") (pintype "unspecified"))
    )
    (net (code "83") (name "Net-(U7-V-)") (class "Default")
      (node (ref "C26") (pin "1") (pinfunction "1_1") (pintype "unspecified"))
      (node (ref "U7") (pin "6") (pinfunction "V-_6") (pintype "unspecified"))
    )
    (net (code "84") (name "VIN24V") (class "Default")
      (node (ref "D1") (pin "1") (pinfunction "1_1") (pintype "unspecified"))
      (node (ref "P9") (pin "1") (pinfunction "1_1") (pintype "unspecified"))
    )
    (net (code "85") (name "unconnected-(FPC3-Pad1)") (class "Default")
      (node (ref "FPC3") (pin "1") (pinfunction "1_1") (pintype "unspecified"))
    )
    (net (code "86") (name "unconnected-(FPC3-Pad2)") (class "Default")
      (node (ref "FPC3") (pin "2") (pinfunction "2_2") (pintype "unspecified"))
    )
    (net (code "87") (name "unconnected-(FPC3-Pad3)") (class "Default")
      (node (ref "FPC3") (pin "3") (pinfunction "3_3") (pintype "unspecified"))
    )
    (net (code "88") (name "unconnected-(FPC3-Pad4)") (class "Default")
      (node (ref "FPC3") (pin "4") (pinfunction "4_4") (pintype "unspecified"))
    )
    (net (code "89") (name "unconnected-(FPC3-Pad18)") (class "Default")
      (node (ref "FPC3") (pin "18") (pinfunction "18_18") (pintype "unspecified"))
    )
    (net (code "90") (name "unconnected-(FPC3-Pad19)") (class "Default")
      (node (ref "FPC3") (pin "19") (pinfunction "19_19") (pintype "unspecified"))
    )
    (net (code "91") (name "unconnected-(FPC3-Pad20)") (class "Default")
      (node (ref "FPC3") (pin "20") (pinfunction "20_20") (pintype "unspecified"))
    )
    (net (code "92") (name "unconnected-(FPC3-Pad27)") (class "Default")
      (node (ref "FPC3") (pin "27") (pinfunction "27_27") (pintype "unspecified"))
    )
    (net (code "93") (name "unconnected-(FPC3-Pad28)") (class "Default")
      (node (ref "FPC3") (pin "28") (pinfunction "28_28") (pintype "unspecified"))
    )
    (net (code "94") (name "unconnected-(FPC3-Pad34)") (class "Default")
      (node (ref "FPC3") (pin "34") (pinfunction "34_34") (pintype "unspecified"))
    )
    (net (code "95") (name "unconnected-(FPC3-Pad35)") (class "Default")
      (node (ref "FPC3") (pin "35") (pinfunction "35_35") (pintype "unspecified"))
    )
    (net (code "96") (name "unconnected-(FPC3-Pad36)") (class "Default")
      (node (ref "FPC3") (pin "36") (pinfunction "36_36") (pintype "unspecified"))
    )
    (net (code "97") (name "unconnected-(FPC4-Pad1)") (class "Default")
      (node (ref "FPC4") (pin "1") (pinfunction "1_1") (pintype "unspecified"))
    )
    (net (code "98") (name "unconnected-(FPC4-Pad2)") (class "Default")
      (node (ref "FPC4") (pin "2") (pinfunction "2_2") (pintype "unspecified"))
    )
    (net (code "99") (name "unconnected-(FPC4-Pad3)") (class "Default")
      (node (ref "FPC4") (pin "3") (pinfunction "3_3") (pintype "unspecified"))
    )
    (net (code "100") (name "unconnected-(FPC4-Pad4)") (class "Default")
      (node (ref "FPC4") (pin "4") (pinfunction "4_4") (pintype "unspecified"))
    )
    (net (code "101") (name "unconnected-(FPC4-Pad5)") (class "Default")
      (node (ref "FPC4") (pin "5") (pinfunction "5_5") (pintype "unspecified"))
    )
    (net (code "102") (name "unconnected-(FPC4-Pad6)") (class "Default")
      (node (ref "FPC4") (pin "6") (pinfunction "6_6") (pintype "unspecified"))
    )
    (net (code "103") (name "unconnected-(FPC4-Pad7)") (class "Default")
      (node (ref "FPC4") (pin "7") (pinfunction "7_7") (pintype "unspecified"))
    )
    (net (code "104") (name "unconnected-(FPC4-Pad8)") (class "Default")
      (node (ref "FPC4") (pin "8") (pinfunction "8_8") (pintype "unspecified"))
    )
    (net (code "105") (name "unconnected-(FPC4-Pad9)") (class "Default")
      (node (ref "FPC4") (pin "9") (pinfunction "9_9") (pintype "unspecified"))
    )
    (net (code "106") (name "unconnected-(FPC4-Pad10)") (class "Default")
      (node (ref "FPC4") (pin "10") (pinfunction "10_10") (pintype "unspecified"))
    )
    (net (code "107") (name "unconnected-(FPC4-Pad11)") (class "Default")
      (node (ref "FPC4") (pin "11") (pinfunction "11_11") (pintype "unspecified"))
    )
    (net (code "108") (name "unconnected-(FPC4-Pad12)") (class "Default")
      (node (ref "FPC4") (pin "12") (pinfunction "12_12") (pintype "unspecified"))
    )
    (net (code "109") (name "unconnected-(FPC4-Pad13)") (class "Default")
      (node (ref "FPC4") (pin "13") (pinfunction "13_13") (pintype "unspecified"))
    )
    (net (code "110") (name "unconnected-(FPC4-Pad14)") (class "Default")
      (node (ref "FPC4") (pin "14") (pinfunction "14_14") (pintype "unspecified"))
    )
    (net (code "111") (name "unconnected-(FPC4-Pad15)") (class "Default")
      (node (ref "FPC4") (pin "15") (pinfunction "15_15") (pintype "unspecified"))
    )
    (net (code "112") (name "unconnected-(FPC4-Pad16)") (class "Default")
      (node (ref "FPC4") (pin "16") (pinfunction "16_16") (pintype "unspecified"))
    )
    (net (code "113") (name "unconnected-(FPC4-Pad17)") (class "Default")
      (node (ref "FPC4") (pin "17") (pinfunction "17_17") (pintype "unspecified"))
    )
    (net (code "114") (name "unconnected-(FPC4-Pad18)") (class "Default")
      (node (ref "FPC4") (pin "18") (pinfunction "18_18") (pintype "unspecified"))
    )
    (net (code "115") (name "unconnected-(FPC4-Pad19)") (class "Default")
      (node (ref "FPC4") (pin "19") (pinfunction "19_19") (pintype "unspecified"))
    )
    (net (code "116") (name "unconnected-(FPC4-Pad20)") (class "Default")
      (node (ref "FPC4") (pin "20") (pinfunction "20_20") (pintype "unspecified"))
    )
    (net (code "117") (name "unconnected-(FPC4-Pad21)") (class "Default")
      (node (ref "FPC4") (pin "21") (pinfunction "21_21") (pintype "unspecified"))
    )
    (net (code "118") (name "unconnected-(FPC4-Pad22)") (class "Default")
      (node (ref "FPC4") (pin "22") (pinfunction "22_22") (pintype "unspecified"))
    )
    (net (code "119") (name "unconnected-(FPC4-Pad23)") (class "Default")
      (node (ref "FPC4") (pin "23") (pinfunction "23_23") (pintype "unspecified"))
    )
    (net (code "120") (name "unconnected-(FPC4-Pad24)") (class "Default")
      (node (ref "FPC4") (pin "24") (pinfunction "24_24") (pintype "unspecified"))
    )
    (net (code "121") (name "unconnected-(FPC4-Pad25)") (class "Default")
      (node (ref "FPC4") (pin "25") (pinfunction "25_25") (pintype "unspecified"))
    )
    (net (code "122") (name "unconnected-(FPC4-Pad26)") (class "Default")
      (node (ref "FPC4") (pin "26") (pinfunction "26_26") (pintype "unspecified"))
    )
    (net (code "123") (name "unconnected-(FPC4-Pad27)") (class "Default")
      (node (ref "FPC4") (pin "27") (pinfunction "27_27") (pintype "unspecified"))
    )
    (net (code "124") (name "unconnected-(FPC4-Pad28)") (class "Default")
      (node (ref "FPC4") (pin "28") (pinfunction "28_28") (pintype "unspecified"))
    )
    (net (code "125") (name "unconnected-(FPC4-Pad29)") (class "Default")
      (node (ref "FPC4") (pin "29") (pinfunction "29_29") (pintype "unspecified"))
    )
    (net (code "126") (name "unconnected-(FPC4-Pad30)") (class "Default")
      (node (ref "FPC4") (pin "30") (pinfunction "30_30") (pintype "unspecified"))
    )
    (net (code "127") (name "unconnected-(FPC4-Pad31)") (class "Default")
      (node (ref "FPC4") (pin "31") (pinfunction "31_31") (pintype "unspecified"))
    )
    (net (code "128") (name "unconnected-(FPC4-Pad32)") (class "Default")
      (node (ref "FPC4") (pin "32") (pinfunction "32_32") (pintype "unspecified"))
    )
    (net (code "129") (name "unconnected-(FPC4-Pad33)") (class "Default")
      (node (ref "FPC4") (pin "33") (pinfunction "33_33") (pintype "unspecified"))
    )
    (net (code "130") (name "unconnected-(FPC4-Pad34)") (class "Default")
      (node (ref "FPC4") (pin "34") (pinfunction "34_34") (pintype "unspecified"))
    )
    (net (code "131") (name "unconnected-(FPC4-Pad35)") (class "Default")
      (node (ref "FPC4") (pin "35") (pinfunction "35_35") (pintype "unspecified"))
    )
    (net (code "132") (name "unconnected-(FPC4-Pad36)") (class "Default")
      (node (ref "FPC4") (pin "36") (pinfunction "36_36") (pintype "unspecified"))
    )
    (net (code "133") (name "unconnected-(FPC4-Pad37)") (class "Default")
      (node (ref "FPC4") (pin "37") (pinfunction "37_37") (pintype "unspecified"))
    )
    (net (code "134") (name "unconnected-(FPC4-Pad38)") (class "Default")
      (node (ref "FPC4") (pin "38") (pinfunction "38_38") (pintype "unspecified"))
    )
    (net (code "135") (name "unconnected-(FPC4-Pad39)") (class "Default")
      (node (ref "FPC4") (pin "39") (pinfunction "39_39") (pintype "unspecified"))
    )
    (net (code "136") (name "unconnected-(FPC4-Pad40)") (class "Default")
      (node (ref "FPC4") (pin "40") (pinfunction "40_40") (pintype "unspecified"))
    )
    (net (code "137") (name "unconnected-(FPC4-Pad41)") (class "Default")
      (node (ref "FPC4") (pin "41") (pinfunction "41_41") (pintype "unspecified"))
    )
    (net (code "138") (name "unconnected-(FPC4-Pad42)") (class "Default")
      (node (ref "FPC4") (pin "42") (pinfunction "42_42") (pintype "unspecified"))
    )
    (net (code "139") (name "unconnected-(U5-NC-Pad28)") (class "Default")
      (node (ref "U5") (pin "28") (pinfunction "NC_28") (pintype "unspecified+no_connect"))
    )
    (net (code "140") (name "unconnected-(U5-NC-Pad29)") (class "Default")
      (node (ref "U5") (pin "29") (pinfunction "NC_29") (pintype "unspecified+no_connect"))
    )
    (net (code "141") (name "unconnected-(U5-NC-Pad30)") (class "Default")
      (node (ref "U5") (pin "30") (pinfunction "NC_30") (pintype "unspecified+no_connect"))
    )
    (net (code "142") (name "unconnected-(U6-CTS#-Pad9)") (class "Default")
      (node (ref "U6") (pin "9") (pinfunction "CTS#_9") (pintype "unspecified"))
    )
    (net (code "143") (name "unconnected-(U6-DCD#-Pad12)") (class "Default")
      (node (ref "U6") (pin "12") (pinfunction "DCD#_12") (pintype "unspecified"))
    )
    (net (code "144") (name "unconnected-(U6-DSR#-Pad10)") (class "Default")
      (node (ref "U6") (pin "10") (pinfunction "DSR#_10") (pintype "unspecified"))
    )
    (net (code "145") (name "unconnected-(U6-R232-Pad15)") (class "Default")
      (node (ref "U6") (pin "15") (pinfunction "R232_15") (pintype "unspecified"))
    )
    (net (code "146") (name "unconnected-(U6-RI#-Pad11)") (class "Default")
      (node (ref "U6") (pin "11") (pinfunction "RI#_11") (pintype "unspecified"))
    )
    (net (code "147") (name "unconnected-(U6-XI-Pad7)") (class "Default")
      (node (ref "U6") (pin "7") (pinfunction "XI_7") (pintype "unspecified"))
    )
    (net (code "148") (name "unconnected-(U6-XO-Pad8)") (class "Default")
      (node (ref "U6") (pin "8") (pinfunction "XO_8") (pintype "unspecified"))
    )
    (net (code "149") (name "unconnected-(U8-DAT1-Pad8)") (class "Default")
      (node (ref "U8") (pin "8") (pinfunction "DAT1_8") (pintype "unspecified"))
    )
    (net (code "150") (name "unconnected-(U8-DAT2-Pad1)") (class "Default")
      (node (ref "U8") (pin "1") (pinfunction "DAT2_1") (pintype "unspecified"))
    )
    (net (code "151") (name "unconnected-(USB2-SBU1-Pad9)") (class "Default")
      (node (ref "USB2") (pin "9") (pinfunction "SBU1_9") (pintype "unspecified+no_connect"))
    )
    (net (code "152") (name "unconnected-(USB2-SBU2-Pad3)") (class "Default")
      (node (ref "USB2") (pin "3") (pinfunction "SBU2_3") (pintype "unspecified+no_connect"))
    )
  )
)
